# BinaryInput.net
KiCad netlist of a schematic drawn in Altium Designer
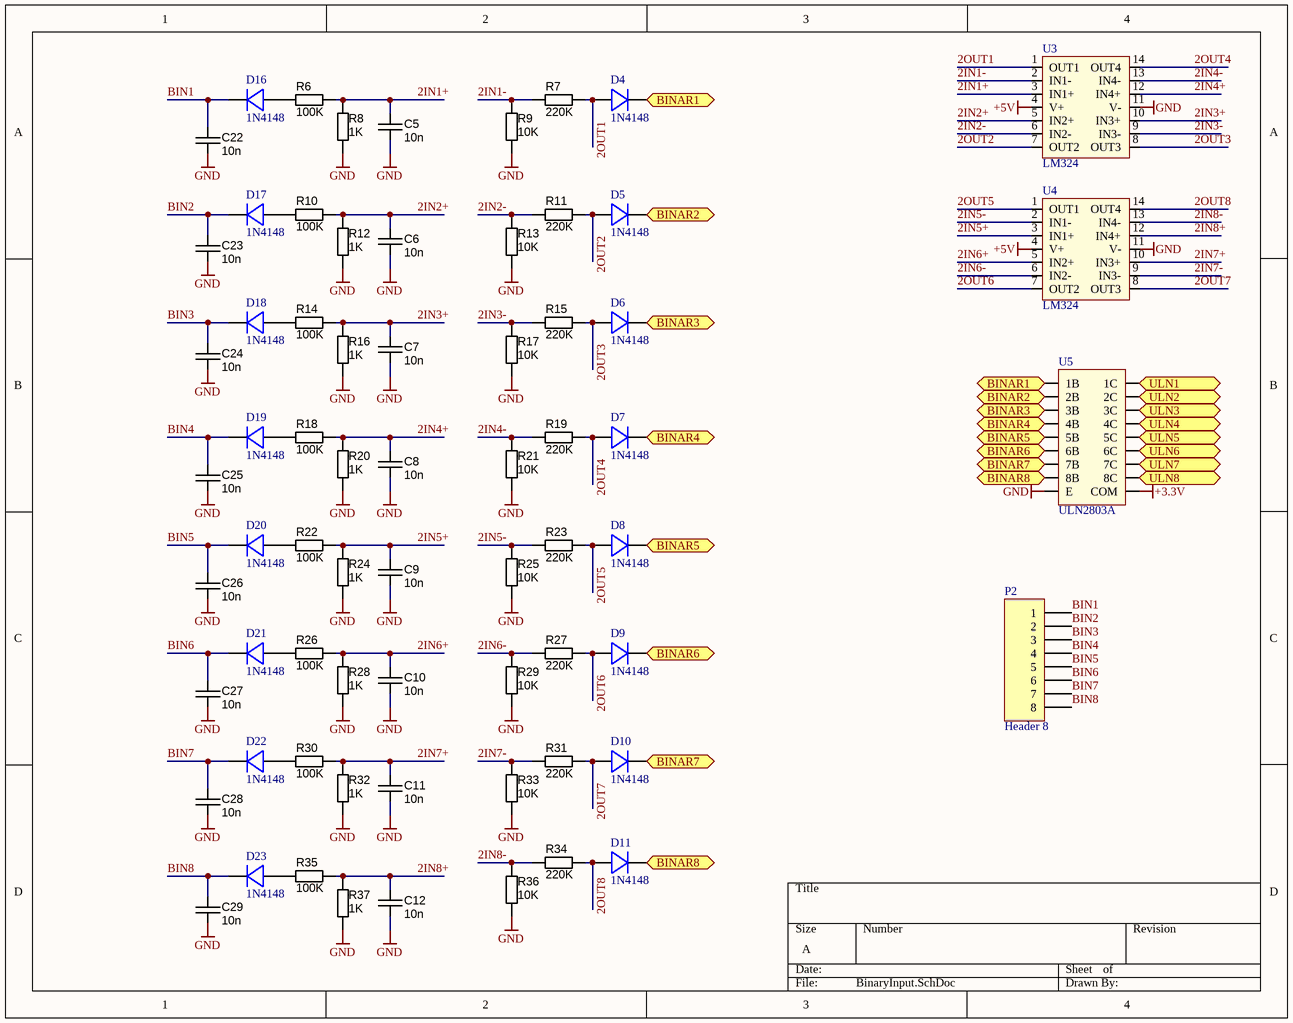
[diagram p0: BinaryInput.SchDoc]

(export (version "E")
  (design (tool "Eeschema 10.0.6"))
  (components
    (comp (ref "C5")
      (value "10n")
      (footprint "CAPC2012X135N")
      (description "Capacitor SMD Cer 10uF 10% 10V X5R 0805")
      (fields (field (name "TOLERANCE") "±10%") (field (name "Comment") "approved sub OK"))
      (libsource (lib "PBL - Capacitors") (part "CAPC_10u_0805_10V"))
    )
    (comp (ref "C6")
      (value "10n")
      (footprint "CAPC2012X135N")
      (description "Capacitor SMD Cer 10uF 10% 10V X5R 0805")
      (fields (field (name "TOLERANCE") "±10%") (field (name "Comment") "approved sub OK"))
      (libsource (lib "PBL - Capacitors") (part "CAPC_10u_0805_10V"))
    )
    (comp (ref "C7")
      (value "10n")
      (footprint "CAPC2012X135N")
      (description "Capacitor SMD Cer 10uF 10% 10V X5R 0805")
      (fields (field (name "TOLERANCE") "±10%") (field (name "Comment") "approved sub OK"))
      (libsource (lib "PBL - Capacitors") (part "CAPC_10u_0805_10V"))
    )
    (comp (ref "C8")
      (value "10n")
      (footprint "CAPC2012X135N")
      (description "Capacitor SMD Cer 10uF 10% 10V X5R 0805")
      (fields (field (name "TOLERANCE") "±10%") (field (name "Comment") "approved sub OK"))
      (libsource (lib "PBL - Capacitors") (part "CAPC_10u_0805_10V"))
    )
    (comp (ref "C9")
      (value "10n")
      (footprint "CAPC2012X135N")
      (description "Capacitor SMD Cer 10uF 10% 10V X5R 0805")
      (fields (field (name "TOLERANCE") "±10%") (field (name "Comment") "approved sub OK"))
      (libsource (lib "PBL - Capacitors") (part "CAPC_10u_0805_10V"))
    )
    (comp (ref "C10")
      (value "10n")
      (footprint "CAPC2012X135N")
      (description "Capacitor SMD Cer 10uF 10% 10V X5R 0805")
      (fields (field (name "TOLERANCE") "±10%") (field (name "Comment") "approved sub OK"))
      (libsource (lib "PBL - Capacitors") (part "CAPC_10u_0805_10V"))
    )
    (comp (ref "C11")
      (value "10n")
      (footprint "CAPC2012X135N")
      (description "Capacitor SMD Cer 10uF 10% 10V X5R 0805")
      (fields (field (name "TOLERANCE") "±10%") (field (name "Comment") "approved sub OK"))
      (libsource (lib "PBL - Capacitors") (part "CAPC_10u_0805_10V"))
    )
    (comp (ref "C12")
      (value "10n")
      (footprint "CAPC2012X135N")
      (description "Capacitor SMD Cer 10uF 10% 10V X5R 0805")
      (fields (field (name "TOLERANCE") "±10%") (field (name "Comment") "approved sub OK"))
      (libsource (lib "PBL - Capacitors") (part "CAPC_10u_0805_10V"))
    )
    (comp (ref "C22")
      (value "10n")
      (footprint "CAPC2012X135N")
      (description "Capacitor SMD Cer 10uF 10% 10V X5R 0805")
      (fields (field (name "TOLERANCE") "±10%") (field (name "Comment") "approved sub OK"))
      (libsource (lib "PBL - Capacitors") (part "CAPC_10u_0805_10V"))
    )
    (comp (ref "C23")
      (value "10n")
      (footprint "CAPC2012X135N")
      (description "Capacitor SMD Cer 10uF 10% 10V X5R 0805")
      (fields (field (name "TOLERANCE") "±10%") (field (name "Comment") "approved sub OK"))
      (libsource (lib "PBL - Capacitors") (part "CAPC_10u_0805_10V"))
    )
    (comp (ref "C24")
      (value "10n")
      (footprint "CAPC2012X135N")
      (description "Capacitor SMD Cer 10uF 10% 10V X5R 0805")
      (fields (field (name "TOLERANCE") "±10%") (field (name "Comment") "approved sub OK"))
      (libsource (lib "PBL - Capacitors") (part "CAPC_10u_0805_10V"))
    )
    (comp (ref "C25")
      (value "10n")
      (footprint "CAPC2012X135N")
      (description "Capacitor SMD Cer 10uF 10% 10V X5R 0805")
      (fields (field (name "TOLERANCE") "±10%") (field (name "Comment") "approved sub OK"))
      (libsource (lib "PBL - Capacitors") (part "CAPC_10u_0805_10V"))
    )
    (comp (ref "C26")
      (value "10n")
      (footprint "CAPC2012X135N")
      (description "Capacitor SMD Cer 10uF 10% 10V X5R 0805")
      (fields (field (name "TOLERANCE") "±10%") (field (name "Comment") "approved sub OK"))
      (libsource (lib "PBL - Capacitors") (part "CAPC_10u_0805_10V"))
    )
    (comp (ref "C27")
      (value "10n")
      (footprint "CAPC2012X135N")
      (description "Capacitor SMD Cer 10uF 10% 10V X5R 0805")
      (fields (field (name "TOLERANCE") "±10%") (field (name "Comment") "approved sub OK"))
      (libsource (lib "PBL - Capacitors") (part "CAPC_10u_0805_10V"))
    )
    (comp (ref "C28")
      (value "10n")
      (footprint "CAPC2012X135N")
      (description "Capacitor SMD Cer 10uF 10% 10V X5R 0805")
      (fields (field (name "TOLERANCE") "±10%") (field (name "Comment") "approved sub OK"))
      (libsource (lib "PBL - Capacitors") (part "CAPC_10u_0805_10V"))
    )
    (comp (ref "C29")
      (value "10n")
      (footprint "CAPC2012X135N")
      (description "Capacitor SMD Cer 10uF 10% 10V X5R 0805")
      (fields (field (name "TOLERANCE") "±10%") (field (name "Comment") "approved sub OK"))
      (libsource (lib "PBL - Capacitors") (part "CAPC_10u_0805_10V"))
    )
    (comp (ref "D4")
      (value "1N4148")
      (footprint "SOD-323")
      (description "Diode SMD SOD-323")
      (libsource (lib "Komponente") (part "D 1N4148"))
    )
    (comp (ref "D5")
      (value "1N4148")
      (footprint "SOD-323")
      (description "Diode SMD SOD-323")
      (libsource (lib "Komponente") (part "D 1N4148"))
    )
    (comp (ref "D6")
      (value "1N4148")
      (footprint "SOD-323")
      (description "Diode SMD SOD-323")
      (libsource (lib "Komponente") (part "D 1N4148"))
    )
    (comp (ref "D7")
      (value "1N4148")
      (footprint "SOD-323")
      (description "Diode SMD SOD-323")
      (libsource (lib "Komponente") (part "D 1N4148"))
    )
    (comp (ref "D8")
      (value "1N4148")
      (footprint "SOD-323")
      (description "Diode SMD SOD-323")
      (libsource (lib "Komponente") (part "D 1N4148"))
    )
    (comp (ref "D9")
      (value "1N4148")
      (footprint "SOD-323")
      (description "Diode SMD SOD-323")
      (libsource (lib "Komponente") (part "D 1N4148"))
    )
    (comp (ref "D10")
      (value "1N4148")
      (footprint "SOD-323")
      (description "Diode SMD SOD-323")
      (libsource (lib "Komponente") (part "D 1N4148"))
    )
    (comp (ref "D11")
      (value "1N4148")
      (footprint "SOD-323")
      (description "Diode SMD SOD-323")
      (libsource (lib "Komponente") (part "D 1N4148"))
    )
    (comp (ref "D16")
      (value "1N4148")
      (footprint "SOD-323")
      (description "Diode SMD SOD-323")
      (libsource (lib "Komponente") (part "D 1N4148"))
    )
    (comp (ref "D17")
      (value "1N4148")
      (footprint "SOD-323")
      (description "Diode SMD SOD-323")
      (libsource (lib "Komponente") (part "D 1N4148"))
    )
    (comp (ref "D18")
      (value "1N4148")
      (footprint "SOD-323")
      (description "Diode SMD SOD-323")
      (libsource (lib "Komponente") (part "D 1N4148"))
    )
    (comp (ref "D19")
      (value "1N4148")
      (footprint "SOD-323")
      (description "Diode SMD SOD-323")
      (libsource (lib "Komponente") (part "D 1N4148"))
    )
    (comp (ref "D20")
      (value "1N4148")
      (footprint "SOD-323")
      (description "Diode SMD SOD-323")
      (libsource (lib "Komponente") (part "D 1N4148"))
    )
    (comp (ref "D21")
      (value "1N4148")
      (footprint "SOD-323")
      (description "Diode SMD SOD-323")
      (libsource (lib "Komponente") (part "D 1N4148"))
    )
    (comp (ref "D22")
      (value "1N4148")
      (footprint "SOD-323")
      (description "Diode SMD SOD-323")
      (libsource (lib "Komponente") (part "D 1N4148"))
    )
    (comp (ref "D23")
      (value "1N4148")
      (footprint "SOD-323")
      (description "Diode SMD SOD-323")
      (libsource (lib "Komponente") (part "D 1N4148"))
    )
    (comp (ref "P2")
      (value "Header 8")
      (footprint "HDR1X8")
      (description "Header, 8-Pin")
      (fields (field (name "PUBLISHER") "Altium Limited"))
      (libsource (lib "Miscellaneous Connectors") (part "Header 8"))
    )
    (comp (ref "R6")
      (value "100K")
      (footprint "RESC2012X70N")
      (description "Resistor SMD chip 10k Ohm 0.125W 1% 0805")
      (fields (field (name "TOLERANCE") "±1%") (field (name "Comment") "Thick Film"))
      (libsource (lib "PBL - Resistors") (part "RES_10K_0805_1%"))
    )
    (comp (ref "R7")
      (value "220K")
      (footprint "RESC2012X70N")
      (description "Resistor SMD chip 10k Ohm 0.125W 1% 0805")
      (fields (field (name "TOLERANCE") "±1%") (field (name "Comment") "Thick Film"))
      (libsource (lib "PBL - Resistors") (part "RES_10K_0805_1%"))
    )
    (comp (ref "R8")
      (value "1K")
      (footprint "RESC2012X70N")
      (description "Resistor SMD chip 10k Ohm 0.125W 1% 0805")
      (fields (field (name "TOLERANCE") "±1%") (field (name "Comment") "Thick Film"))
      (libsource (lib "") (part "RES_10K_0805_1%_1"))
    )
    (comp (ref "R9")
      (value "10K")
      (footprint "RESC2012X70N")
      (description "Resistor SMD chip 10k Ohm 0.125W 1% 0805")
      (fields (field (name "TOLERANCE") "±1%") (field (name "Comment") "Thick Film"))
      (libsource (lib "") (part "RES_10K_0805_1%_1"))
    )
    (comp (ref "R10")
      (value "100K")
      (footprint "RESC2012X70N")
      (description "Resistor SMD chip 10k Ohm 0.125W 1% 0805")
      (fields (field (name "TOLERANCE") "±1%") (field (name "Comment") "Thick Film"))
      (libsource (lib "PBL - Resistors") (part "RES_10K_0805_1%"))
    )
    (comp (ref "R11")
      (value "220K")
      (footprint "RESC2012X70N")
      (description "Resistor SMD chip 10k Ohm 0.125W 1% 0805")
      (fields (field (name "TOLERANCE") "±1%") (field (name "Comment") "Thick Film"))
      (libsource (lib "PBL - Resistors") (part "RES_10K_0805_1%"))
    )
    (comp (ref "R12")
      (value "1K")
      (footprint "RESC2012X70N")
      (description "Resistor SMD chip 10k Ohm 0.125W 1% 0805")
      (fields (field (name "TOLERANCE") "±1%") (field (name "Comment") "Thick Film"))
      (libsource (lib "") (part "RES_10K_0805_1%_1"))
    )
    (comp (ref "R13")
      (value "10K")
      (footprint "RESC2012X70N")
      (description "Resistor SMD chip 10k Ohm 0.125W 1% 0805")
      (fields (field (name "TOLERANCE") "±1%") (field (name "Comment") "Thick Film"))
      (libsource (lib "") (part "RES_10K_0805_1%_1"))
    )
    (comp (ref "R14")
      (value "100K")
      (footprint "RESC2012X70N")
      (description "Resistor SMD chip 10k Ohm 0.125W 1% 0805")
      (fields (field (name "TOLERANCE") "±1%") (field (name "Comment") "Thick Film"))
      (libsource (lib "PBL - Resistors") (part "RES_10K_0805_1%"))
    )
    (comp (ref "R15")
      (value "220K")
      (footprint "RESC2012X70N")
      (description "Resistor SMD chip 10k Ohm 0.125W 1% 0805")
      (fields (field (name "TOLERANCE") "±1%") (field (name "Comment") "Thick Film"))
      (libsource (lib "PBL - Resistors") (part "RES_10K_0805_1%"))
    )
    (comp (ref "R16")
      (value "1K")
      (footprint "RESC2012X70N")
      (description "Resistor SMD chip 10k Ohm 0.125W 1% 0805")
      (fields (field (name "TOLERANCE") "±1%") (field (name "Comment") "Thick Film"))
      (libsource (lib "") (part "RES_10K_0805_1%_1"))
    )
    (comp (ref "R17")
      (value "10K")
      (footprint "RESC2012X70N")
      (description "Resistor SMD chip 10k Ohm 0.125W 1% 0805")
      (fields (field (name "TOLERANCE") "±1%") (field (name "Comment") "Thick Film"))
      (libsource (lib "") (part "RES_10K_0805_1%_1"))
    )
    (comp (ref "R18")
      (value "100K")
      (footprint "RESC2012X70N")
      (description "Resistor SMD chip 10k Ohm 0.125W 1% 0805")
      (fields (field (name "TOLERANCE") "±1%") (field (name "Comment") "Thick Film"))
      (libsource (lib "PBL - Resistors") (part "RES_10K_0805_1%"))
    )
    (comp (ref "R19")
      (value "220K")
      (footprint "RESC2012X70N")
      (description "Resistor SMD chip 10k Ohm 0.125W 1% 0805")
      (fields (field (name "TOLERANCE") "±1%") (field (name "Comment") "Thick Film"))
      (libsource (lib "PBL - Resistors") (part "RES_10K_0805_1%"))
    )
    (comp (ref "R20")
      (value "1K")
      (footprint "RESC2012X70N")
      (description "Resistor SMD chip 10k Ohm 0.125W 1% 0805")
      (fields (field (name "TOLERANCE") "±1%") (field (name "Comment") "Thick Film"))
      (libsource (lib "") (part "RES_10K_0805_1%_1"))
    )
    (comp (ref "R21")
      (value "10K")
      (footprint "RESC2012X70N")
      (description "Resistor SMD chip 10k Ohm 0.125W 1% 0805")
      (fields (field (name "TOLERANCE") "±1%") (field (name "Comment") "Thick Film"))
      (libsource (lib "") (part "RES_10K_0805_1%_1"))
    )
    (comp (ref "R22")
      (value "100K")
      (footprint "RESC2012X70N")
      (description "Resistor SMD chip 10k Ohm 0.125W 1% 0805")
      (fields (field (name "TOLERANCE") "±1%") (field (name "Comment") "Thick Film"))
      (libsource (lib "PBL - Resistors") (part "RES_10K_0805_1%"))
    )
    (comp (ref "R23")
      (value "220K")
      (footprint "RESC2012X70N")
      (description "Resistor SMD chip 10k Ohm 0.125W 1% 0805")
      (fields (field (name "TOLERANCE") "±1%") (field (name "Comment") "Thick Film"))
      (libsource (lib "PBL - Resistors") (part "RES_10K_0805_1%"))
    )
    (comp (ref "R24")
      (value "1K")
      (footprint "RESC2012X70N")
      (description "Resistor SMD chip 10k Ohm 0.125W 1% 0805")
      (fields (field (name "TOLERANCE") "±1%") (field (name "Comment") "Thick Film"))
      (libsource (lib "") (part "RES_10K_0805_1%_1"))
    )
    (comp (ref "R25")
      (value "10K")
      (footprint "RESC2012X70N")
      (description "Resistor SMD chip 10k Ohm 0.125W 1% 0805")
      (fields (field (name "TOLERANCE") "±1%") (field (name "Comment") "Thick Film"))
      (libsource (lib "") (part "RES_10K_0805_1%_1"))
    )
    (comp (ref "R26")
      (value "100K")
      (footprint "RESC2012X70N")
      (description "Resistor SMD chip 10k Ohm 0.125W 1% 0805")
      (fields (field (name "TOLERANCE") "±1%") (field (name "Comment") "Thick Film"))
      (libsource (lib "PBL - Resistors") (part "RES_10K_0805_1%"))
    )
    (comp (ref "R27")
      (value "220K")
      (footprint "RESC2012X70N")
      (description "Resistor SMD chip 10k Ohm 0.125W 1% 0805")
      (fields (field (name "TOLERANCE") "±1%") (field (name "Comment") "Thick Film"))
      (libsource (lib "PBL - Resistors") (part "RES_10K_0805_1%"))
    )
    (comp (ref "R28")
      (value "1K")
      (footprint "RESC2012X70N")
      (description "Resistor SMD chip 10k Ohm 0.125W 1% 0805")
      (fields (field (name "TOLERANCE") "±1%") (field (name "Comment") "Thick Film"))
      (libsource (lib "") (part "RES_10K_0805_1%_1"))
    )
    (comp (ref "R29")
      (value "10K")
      (footprint "RESC2012X70N")
      (description "Resistor SMD chip 10k Ohm 0.125W 1% 0805")
      (fields (field (name "TOLERANCE") "±1%") (field (name "Comment") "Thick Film"))
      (libsource (lib "") (part "RES_10K_0805_1%_1"))
    )
    (comp (ref "R30")
      (value "100K")
      (footprint "RESC2012X70N")
      (description "Resistor SMD chip 10k Ohm 0.125W 1% 0805")
      (fields (field (name "TOLERANCE") "±1%") (field (name "Comment") "Thick Film"))
      (libsource (lib "PBL - Resistors") (part "RES_10K_0805_1%"))
    )
    (comp (ref "R31")
      (value "220K")
      (footprint "RESC2012X70N")
      (description "Resistor SMD chip 10k Ohm 0.125W 1% 0805")
      (fields (field (name "TOLERANCE") "±1%") (field (name "Comment") "Thick Film"))
      (libsource (lib "PBL - Resistors") (part "RES_10K_0805_1%"))
    )
    (comp (ref "R32")
      (value "1K")
      (footprint "RESC2012X70N")
      (description "Resistor SMD chip 10k Ohm 0.125W 1% 0805")
      (fields (field (name "TOLERANCE") "±1%") (field (name "Comment") "Thick Film"))
      (libsource (lib "") (part "RES_10K_0805_1%_1"))
    )
    (comp (ref "R33")
      (value "10K")
      (footprint "RESC2012X70N")
      (description "Resistor SMD chip 10k Ohm 0.125W 1% 0805")
      (fields (field (name "TOLERANCE") "±1%") (field (name "Comment") "Thick Film"))
      (libsource (lib "") (part "RES_10K_0805_1%_1"))
    )
    (comp (ref "R34")
      (value "220K")
      (footprint "RESC2012X70N")
      (description "Resistor SMD chip 10k Ohm 0.125W 1% 0805")
      (fields (field (name "TOLERANCE") "±1%") (field (name "Comment") "Thick Film"))
      (libsource (lib "PBL - Resistors") (part "RES_10K_0805_1%"))
    )
    (comp (ref "R35")
      (value "100K")
      (footprint "RESC2012X70N")
      (description "Resistor SMD chip 10k Ohm 0.125W 1% 0805")
      (fields (field (name "TOLERANCE") "±1%") (field (name "Comment") "Thick Film"))
      (libsource (lib "PBL - Resistors") (part "RES_10K_0805_1%"))
    )
    (comp (ref "R36")
      (value "10K")
      (footprint "RESC2012X70N")
      (description "Resistor SMD chip 10k Ohm 0.125W 1% 0805")
      (fields (field (name "TOLERANCE") "±1%") (field (name "Comment") "Thick Film"))
      (libsource (lib "") (part "RES_10K_0805_1%_1"))
    )
    (comp (ref "R37")
      (value "1K")
      (footprint "RESC2012X70N")
      (description "Resistor SMD chip 10k Ohm 0.125W 1% 0805")
      (fields (field (name "TOLERANCE") "±1%") (field (name "Comment") "Thick Film"))
      (libsource (lib "") (part "RES_10K_0805_1%_1"))
    )
    (comp (ref "U3") (value "LM324") (footprint "SOIC14") (libsource (lib "AltiumLibrary") (part "LM324")))
    (comp (ref "U4") (value "LM324") (footprint "SOIC14") (libsource (lib "AltiumLibrary") (part "LM324")))
    (comp (ref "U5")
      (value "ULN2803A")
      (footprint "SOP18")
      (description "Darlington Transistor Arrays")
      (libsource (lib "Lib_darijo") (part "ULN2803A"))
    )
  )
  (nets
    (net (code "1") (name "+3.3V") (class "Default")
      (node (ref "U5") (pin "10") (pinfunction "COM_10") (pintype "passive"))
    )
    (net (code "2") (name "+5V") (class "Default")
      (node (ref "U3") (pin "4") (pinfunction "V+_4") (pintype "passive"))
      (node (ref "U4") (pin "4") (pinfunction "V+_4") (pintype "passive"))
    )
    (net (code "3") (name "/2IN1+") (class "Default")
      (node (ref "C5") (pin "1") (pintype "passive"))
      (node (ref "R6") (pin "2") (pinfunction "2_2") (pintype "passive"))
      (node (ref "R8") (pin "2") (pinfunction "2_2") (pintype "passive"))
      (node (ref "U3") (pin "3") (pinfunction "IN1+_3") (pintype "passive"))
    )
    (net (code "4") (name "/2IN1-") (class "Default")
      (node (ref "R7") (pin "1") (pinfunction "1_1") (pintype "passive"))
      (node (ref "R9") (pin "2") (pinfunction "2_2") (pintype "passive"))
      (node (ref "U3") (pin "2") (pinfunction "IN1-_2") (pintype "passive"))
    )
    (net (code "5") (name "/2IN2+") (class "Default")
      (node (ref "C6") (pin "1") (pintype "passive"))
      (node (ref "R10") (pin "2") (pinfunction "2_2") (pintype "passive"))
      (node (ref "R12") (pin "2") (pinfunction "2_2") (pintype "passive"))
      (node (ref "U3") (pin "5") (pinfunction "IN2+_5") (pintype "passive"))
    )
    (net (code "6") (name "/2IN2-") (class "Default")
      (node (ref "R11") (pin "1") (pinfunction "1_1") (pintype "passive"))
      (node (ref "R13") (pin "2") (pinfunction "2_2") (pintype "passive"))
      (node (ref "U3") (pin "6") (pinfunction "IN2-_6") (pintype "passive"))
    )
    (net (code "7") (name "/2IN3+") (class "Default")
      (node (ref "C7") (pin "1") (pintype "passive"))
      (node (ref "R14") (pin "2") (pinfunction "2_2") (pintype "passive"))
      (node (ref "R16") (pin "2") (pinfunction "2_2") (pintype "passive"))
      (node (ref "U3") (pin "10") (pinfunction "IN3+_10") (pintype "passive"))
    )
    (net (code "8") (name "/2IN3-") (class "Default")
      (node (ref "R15") (pin "1") (pinfunction "1_1") (pintype "passive"))
      (node (ref "R17") (pin "2") (pinfunction "2_2") (pintype "passive"))
      (node (ref "U3") (pin "9") (pinfunction "IN3-_9") (pintype "passive"))
    )
    (net (code "9") (name "/2IN4+") (class "Default")
      (node (ref "C8") (pin "1") (pintype "passive"))
      (node (ref "R18") (pin "2") (pinfunction "2_2") (pintype "passive"))
      (node (ref "R20") (pin "2") (pinfunction "2_2") (pintype "passive"))
      (node (ref "U3") (pin "12") (pinfunction "IN4+_12") (pintype "passive"))
    )
    (net (code "10") (name "/2IN4-") (class "Default")
      (node (ref "R19") (pin "1") (pinfunction "1_1") (pintype "passive"))
      (node (ref "R21") (pin "2") (pinfunction "2_2") (pintype "passive"))
      (node (ref "U3") (pin "13") (pinfunction "IN4-_13") (pintype "passive"))
    )
    (net (code "11") (name "/2IN5+") (class "Default")
      (node (ref "C9") (pin "1") (pintype "passive"))
      (node (ref "R22") (pin "2") (pinfunction "2_2") (pintype "passive"))
      (node (ref "R24") (pin "2") (pinfunction "2_2") (pintype "passive"))
      (node (ref "U4") (pin "3") (pinfunction "IN1+_3") (pintype "passive"))
    )
    (net (code "12") (name "/2IN5-") (class "Default")
      (node (ref "R23") (pin "1") (pinfunction "1_1") (pintype "passive"))
      (node (ref "R25") (pin "2") (pinfunction "2_2") (pintype "passive"))
      (node (ref "U4") (pin "2") (pinfunction "IN1-_2") (pintype "passive"))
    )
    (net (code "13") (name "/2IN6+") (class "Default")
      (node (ref "C10") (pin "1") (pintype "passive"))
      (node (ref "R26") (pin "2") (pinfunction "2_2") (pintype "passive"))
      (node (ref "R28") (pin "2") (pinfunction "2_2") (pintype "passive"))
      (node (ref "U4") (pin "5") (pinfunction "IN2+_5") (pintype "passive"))
    )
    (net (code "14") (name "/2IN6-") (class "Default")
      (node (ref "R27") (pin "1") (pinfunction "1_1") (pintype "passive"))
      (node (ref "R29") (pin "2") (pinfunction "2_2") (pintype "passive"))
      (node (ref "U4") (pin "6") (pinfunction "IN2-_6") (pintype "passive"))
    )
    (net (code "15") (name "/2IN7+") (class "Default")
      (node (ref "C11") (pin "1") (pintype "passive"))
      (node (ref "R30") (pin "2") (pinfunction "2_2") (pintype "passive"))
      (node (ref "R32") (pin "2") (pinfunction "2_2") (pintype "passive"))
      (node (ref "U4") (pin "10") (pinfunction "IN3+_10") (pintype "passive"))
    )
    (net (code "16") (name "/2IN7-") (class "Default")
      (node (ref "R31") (pin "1") (pinfunction "1_1") (pintype "passive"))
      (node (ref "R33") (pin "2") (pinfunction "2_2") (pintype "passive"))
      (node (ref "U4") (pin "9") (pinfunction "IN3-_9") (pintype "passive"))
    )
    (net (code "17") (name "/2IN8+") (class "Default")
      (node (ref "C12") (pin "1") (pintype "passive"))
      (node (ref "R35") (pin "2") (pinfunction "2_2") (pintype "passive"))
      (node (ref "R37") (pin "2") (pinfunction "2_2") (pintype "passive"))
      (node (ref "U4") (pin "12") (pinfunction "IN4+_12") (pintype "passive"))
    )
    (net (code "18") (name "/2IN8-") (class "Default")
      (node (ref "R34") (pin "1") (pinfunction "1_1") (pintype "passive"))
      (node (ref "R36") (pin "2") (pinfunction "2_2") (pintype "passive"))
      (node (ref "U4") (pin "13") (pinfunction "IN4-_13") (pintype "passive"))
    )
    (net (code "19") (name "/2OUT1") (class "Default")
      (node (ref "D4") (pin "1") (pinfunction "A_1") (pintype "passive"))
      (node (ref "R7") (pin "2") (pinfunction "2_2") (pintype "passive"))
      (node (ref "U3") (pin "1") (pinfunction "OUT1_1") (pintype "passive"))
    )
    (net (code "20") (name "/2OUT2") (class "Default")
      (node (ref "D5") (pin "1") (pinfunction "A_1") (pintype "passive"))
      (node (ref "R11") (pin "2") (pinfunction "2_2") (pintype "passive"))
      (node (ref "U3") (pin "7") (pinfunction "OUT2_7") (pintype "passive"))
    )
    (net (code "21") (name "/2OUT3") (class "Default")
      (node (ref "D6") (pin "1") (pinfunction "A_1") (pintype "passive"))
      (node (ref "R15") (pin "2") (pinfunction "2_2") (pintype "passive"))
      (node (ref "U3") (pin "8") (pinfunction "OUT3_8") (pintype "passive"))
    )
    (net (code "22") (name "/2OUT4") (class "Default")
      (node (ref "D7") (pin "1") (pinfunction "A_1") (pintype "passive"))
      (node (ref "R19") (pin "2") (pinfunction "2_2") (pintype "passive"))
      (node (ref "U3") (pin "14") (pinfunction "OUT4_14") (pintype "passive"))
    )
    (net (code "23") (name "/2OUT5") (class "Default")
      (node (ref "D8") (pin "1") (pinfunction "A_1") (pintype "passive"))
      (node (ref "R23") (pin "2") (pinfunction "2_2") (pintype "passive"))
      (node (ref "U4") (pin "1") (pinfunction "OUT1_1") (pintype "passive"))
    )
    (net (code "24") (name "/2OUT6") (class "Default")
      (node (ref "D9") (pin "1") (pinfunction "A_1") (pintype "passive"))
      (node (ref "R27") (pin "2") (pinfunction "2_2") (pintype "passive"))
      (node (ref "U4") (pin "7") (pinfunction "OUT2_7") (pintype "passive"))
    )
    (net (code "25") (name "/2OUT7") (class "Default")
      (node (ref "D10") (pin "1") (pinfunction "A_1") (pintype "passive"))
      (node (ref "R31") (pin "2") (pinfunction "2_2") (pintype "passive"))
      (node (ref "U4") (pin "8") (pinfunction "OUT3_8") (pintype "passive"))
    )
    (net (code "26") (name "/2OUT8") (class "Default")
      (node (ref "D11") (pin "1") (pinfunction "A_1") (pintype "passive"))
      (node (ref "R34") (pin "2") (pinfunction "2_2") (pintype "passive"))
      (node (ref "U4") (pin "14") (pinfunction "OUT4_14") (pintype "passive"))
    )
    (net (code "27") (name "/BIN1") (class "Default")
      (node (ref "C22") (pin "1") (pintype "passive"))
      (node (ref "D16") (pin "2") (pinfunction "K_2") (pintype "passive"))
      (node (ref "P2") (pin "1") (pinfunction "1_1") (pintype "passive"))
    )
    (net (code "28") (name "/BIN2") (class "Default")
      (node (ref "C23") (pin "1") (pintype "passive"))
      (node (ref "D17") (pin "2") (pinfunction "K_2") (pintype "passive"))
      (node (ref "P2") (pin "2") (pinfunction "2_2") (pintype "passive"))
    )
    (net (code "29") (name "/BIN3") (class "Default")
      (node (ref "C24") (pin "1") (pintype "passive"))
      (node (ref "D18") (pin "2") (pinfunction "K_2") (pintype "passive"))
      (node (ref "P2") (pin "3") (pinfunction "3_3") (pintype "passive"))
    )
    (net (code "30") (name "/BIN4") (class "Default")
      (node (ref "C25") (pin "1") (pintype "passive"))
      (node (ref "D19") (pin "2") (pinfunction "K_2") (pintype "passive"))
      (node (ref "P2") (pin "4") (pinfunction "4_4") (pintype "passive"))
    )
    (net (code "31") (name "/BIN5") (class "Default")
      (node (ref "C26") (pin "1") (pintype "passive"))
      (node (ref "D20") (pin "2") (pinfunction "K_2") (pintype "passive"))
      (node (ref "P2") (pin "5") (pinfunction "5_5") (pintype "passive"))
    )
    (net (code "32") (name "/BIN6") (class "Default")
      (node (ref "C27") (pin "1") (pintype "passive"))
      (node (ref "D21") (pin "2") (pinfunction "K_2") (pintype "passive"))
      (node (ref "P2") (pin "6") (pinfunction "6_6") (pintype "passive"))
    )
    (net (code "33") (name "/BIN7") (class "Default")
      (node (ref "C28") (pin "1") (pintype "passive"))
      (node (ref "D22") (pin "2") (pinfunction "K_2") (pintype "passive"))
      (node (ref "P2") (pin "7") (pinfunction "7_7") (pintype "passive"))
    )
    (net (code "34") (name "/BIN8") (class "Default")
      (node (ref "C29") (pin "1") (pintype "passive"))
      (node (ref "D23") (pin "2") (pinfunction "K_2") (pintype "passive"))
      (node (ref "P2") (pin "8") (pinfunction "8_8") (pintype "passive"))
    )
    (net (code "35") (name "/BINAR1") (class "Default")
      (node (ref "D4") (pin "2") (pinfunction "K_2") (pintype "passive"))
      (node (ref "U5") (pin "1") (pinfunction "1B_1") (pintype "passive"))
    )
    (net (code "36") (name "/BINAR2") (class "Default")
      (node (ref "D5") (pin "2") (pinfunction "K_2") (pintype "passive"))
      (node (ref "U5") (pin "2") (pinfunction "2B_2") (pintype "passive"))
    )
    (net (code "37") (name "/BINAR3") (class "Default")
      (node (ref "D6") (pin "2") (pinfunction "K_2") (pintype "passive"))
      (node (ref "U5") (pin "3") (pinfunction "3B_3") (pintype "passive"))
    )
    (net (code "38") (name "/BINAR4") (class "Default")
      (node (ref "D7") (pin "2") (pinfunction "K_2") (pintype "passive"))
      (node (ref "U5") (pin "4") (pinfunction "4B_4") (pintype "passive"))
    )
    (net (code "39") (name "/BINAR5") (class "Default")
      (node (ref "D8") (pin "2") (pinfunction "K_2") (pintype "passive"))
      (node (ref "U5") (pin "5") (pinfunction "5B_5") (pintype "passive"))
    )
    (net (code "40") (name "/BINAR6") (class "Default")
      (node (ref "D9") (pin "2") (pinfunction "K_2") (pintype "passive"))
      (node (ref "U5") (pin "6") (pinfunction "6B_6") (pintype "passive"))
    )
    (net (code "41") (name "/BINAR7") (class "Default")
      (node (ref "D10") (pin "2") (pinfunction "K_2") (pintype "passive"))
      (node (ref "U5") (pin "7") (pinfunction "7B_7") (pintype "passive"))
    )
    (net (code "42") (name "/BINAR8") (class "Default")
      (node (ref "D11") (pin "2") (pinfunction "K_2") (pintype "passive"))
      (node (ref "U5") (pin "8") (pinfunction "8B_8") (pintype "passive"))
    )
    (net (code "43") (name "/ULN1") (class "Default")
      (node (ref "U5") (pin "18") (pinfunction "1C_18") (pintype "passive"))
    )
    (net (code "44") (name "/ULN2") (class "Default")
      (node (ref "U5") (pin "17") (pinfunction "2C_17") (pintype "passive"))
    )
    (net (code "45") (name "/ULN3") (class "Default")
      (node (ref "U5") (pin "16") (pinfunction "3C_16") (pintype "passive"))
    )
    (net (code "46") (name "/ULN4") (class "Default")
      (node (ref "U5") (pin "15") (pinfunction "4C_15") (pintype "passive"))
    )
    (net (code "47") (name "/ULN5") (class "Default")
      (node (ref "U5") (pin "14") (pinfunction "5C_14") (pintype "passive"))
    )
    (net (code "48") (name "/ULN6") (class "Default")
      (node (ref "U5") (pin "13") (pinfunction "6C_13") (pintype "passive"))
    )
    (net (code "49") (name "/ULN7") (class "Default")
      (node (ref "U5") (pin "12") (pinfunction "7C_12") (pintype "passive"))
    )
    (net (code "50") (name "/ULN8") (class "Default")
      (node (ref "U5") (pin "11") (pinfunction "8C_11") (pintype "passive"))
    )
    (net (code "51") (name "GND") (class "Default")
      (node (ref "C10") (pin "2") (pintype "passive"))
      (node (ref "C11") (pin "2") (pintype "passive"))
      (node (ref "C12") (pin "2") (pintype "passive"))
      (node (ref "C22") (pin "2") (pintype "passive"))
      (node (ref "C23") (pin "2") (pintype "passive"))
      (node (ref "C24") (pin "2") (pintype "passive"))
      (node (ref "C25") (pin "2") (pintype "passive"))
      (node (ref "C26") (pin "2") (pintype "passive"))
      (node (ref "C27") (pin "2") (pintype "passive"))
      (node (ref "C28") (pin "2") (pintype "passive"))
      (node (ref "C29") (pin "2") (pintype "passive"))
      (node (ref "C5") (pin "2") (pintype "passive"))
      (node (ref "C6") (pin "2") (pintype "passive"))
      (node (ref "C7") (pin "2") (pintype "passive"))
      (node (ref "C8") (pin "2") (pintype "passive"))
      (node (ref "C9") (pin "2") (pintype "passive"))
      (node (ref "R12") (pin "1") (pinfunction "1_1") (pintype "passive"))
      (node (ref "R13") (pin "1") (pinfunction "1_1") (pintype "passive"))
      (node (ref "R16") (pin "1") (pinfunction "1_1") (pintype "passive"))
      (node (ref "R17") (pin "1") (pinfunction "1_1") (pintype "passive"))
      (node (ref "R20") (pin "1") (pinfunction "1_1") (pintype "passive"))
      (node (ref "R21") (pin "1") (pinfunction "1_1") (pintype "passive"))
      (node (ref "R24") (pin "1") (pinfunction "1_1") (pintype "passive"))
      (node (ref "R25") (pin "1") (pinfunction "1_1") (pintype "passive"))
      (node (ref "R28") (pin "1") (pinfunction "1_1") (pintype "passive"))
      (node (ref "R29") (pin "1") (pinfunction "1_1") (pintype "passive"))
      (node (ref "R32") (pin "1") (pinfunction "1_1") (pintype "passive"))
      (node (ref "R33") (pin "1") (pinfunction "1_1") (pintype "passive"))
      (node (ref "R36") (pin "1") (pinfunction "1_1") (pintype "passive"))
      (node (ref "R37") (pin "1") (pinfunction "1_1") (pintype "passive"))
      (node (ref "R8") (pin "1") (pinfunction "1_1") (pintype "passive"))
      (node (ref "R9") (pin "1") (pinfunction "1_1") (pintype "passive"))
      (node (ref "U3") (pin "11") (pinfunction "V-_11") (pintype "passive"))
      (node (ref "U4") (pin "11") (pinfunction "V-_11") (pintype "passive"))
      (node (ref "U5") (pin "9") (pinfunction "E_9") (pintype "passive"))
    )
    (net (code "52") (name "Net-(D16-A)") (class "Default")
      (node (ref "D16") (pin "1") (pinfunction "A_1") (pintype "passive"))
      (node (ref "R6") (pin "1") (pinfunction "1_1") (pintype "passive"))
    )
    (net (code "53") (name "Net-(D17-A)") (class "Default")
      (node (ref "D17") (pin "1") (pinfunction "A_1") (pintype "passive"))
      (node (ref "R10") (pin "1") (pinfunction "1_1") (pintype "passive"))
    )
    (net (code "54") (name "Net-(D18-A)") (class "Default")
      (node (ref "D18") (pin "1") (pinfunction "A_1") (pintype "passive"))
      (node (ref "R14") (pin "1") (pinfunction "1_1") (pintype "passive"))
    )
    (net (code "55") (name "Net-(D19-A)") (class "Default")
      (node (ref "D19") (pin "1") (pinfunction "A_1") (pintype "passive"))
      (node (ref "R18") (pin "1") (pinfunction "1_1") (pintype "passive"))
    )
    (net (code "56") (name "Net-(D20-A)") (class "Default")
      (node (ref "D20") (pin "1") (pinfunction "A_1") (pintype "passive"))
      (node (ref "R22") (pin "1") (pinfunction "1_1") (pintype "passive"))
    )
    (net (code "57") (name "Net-(D21-A)") (class "Default")
      (node (ref "D21") (pin "1") (pinfunction "A_1") (pintype "passive"))
      (node (ref "R26") (pin "1") (pinfunction "1_1") (pintype "passive"))
    )
    (net (code "58") (name "Net-(D22-A)") (class "Default")
      (node (ref "D22") (pin "1") (pinfunction "A_1") (pintype "passive"))
      (node (ref "R30") (pin "1") (pinfunction "1_1") (pintype "passive"))
    )
    (net (code "59") (name "Net-(D23-A)") (class "Default")
      (node (ref "D23") (pin "1") (pinfunction "A_1") (pintype "passive"))
      (node (ref "R35") (pin "1") (pinfunction "1_1") (pintype "passive"))
    )
  )
)
